# Connector.net
KiCad netlist of a schematic drawn in Altium Designer
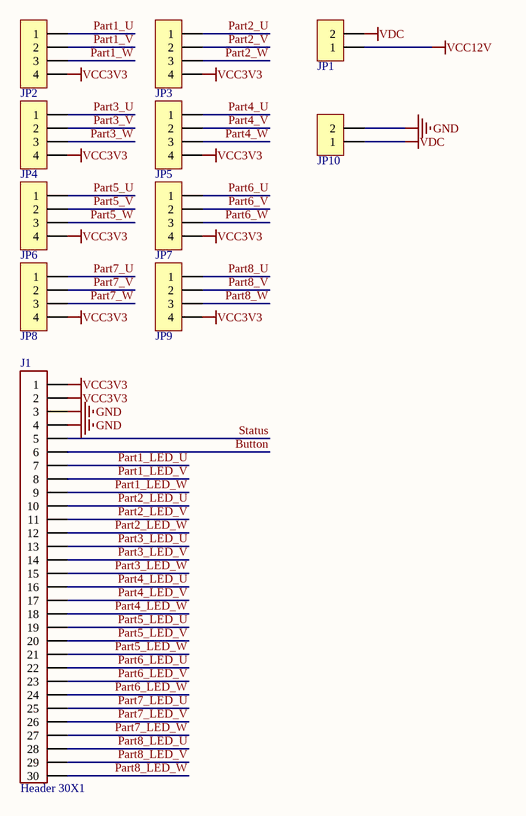
[diagram p0: Connector.SchDoc]

(export (version "E")
  (design (tool "Eeschema 10.0.6"))
  (components
    (comp (ref "J1")
      (value "Header 30X1")
      (footprint "FPC1.0-2H-WS-30P")
      (libsource (lib "Connector-PinHeader") (part "Header 30X1"))
    )
    (comp (ref "JP1")
      (value "HDR-1X2")
      (footprint "XH2.54-LI-2P")
      (description "2P接插件")
      (fields (field (name "版权归属") "源创客"))
      (libsource (lib "Connector-PinHeader") (part "Header 2"))
    )
    (comp (ref "JP2")
      (value "HDR-1X4")
      (footprint "XH2.54-LI-4P")
      (description "4P接插件")
      (fields (field (name "版权归属") "源创客"))
      (libsource (lib "Connector-PinHeader") (part "Header 4"))
    )
    (comp (ref "JP3")
      (value "HDR-1X4")
      (footprint "XH2.54-LI-4P")
      (description "4P接插件")
      (fields (field (name "版权归属") "源创客"))
      (libsource (lib "Connector-PinHeader") (part "Header 4"))
    )
    (comp (ref "JP4")
      (value "HDR-1X4")
      (footprint "XH2.54-LI-4P")
      (description "4P接插件")
      (fields (field (name "版权归属") "源创客"))
      (libsource (lib "Connector-PinHeader") (part "Header 4"))
    )
    (comp (ref "JP5")
      (value "HDR-1X4")
      (footprint "XH2.54-LI-4P")
      (description "4P接插件")
      (fields (field (name "版权归属") "源创客"))
      (libsource (lib "Connector-PinHeader") (part "Header 4"))
    )
    (comp (ref "JP6")
      (value "HDR-1X4")
      (footprint "XH2.54-LI-4P")
      (description "4P接插件")
      (fields (field (name "版权归属") "源创客"))
      (libsource (lib "Connector-PinHeader") (part "Header 4"))
    )
    (comp (ref "JP7")
      (value "HDR-1X4")
      (footprint "XH2.54-LI-4P")
      (description "4P接插件")
      (fields (field (name "版权归属") "源创客"))
      (libsource (lib "Connector-PinHeader") (part "Header 4"))
    )
    (comp (ref "JP8")
      (value "HDR-1X4")
      (footprint "XH2.54-LI-4P")
      (description "4P接插件")
      (fields (field (name "版权归属") "源创客"))
      (libsource (lib "Connector-PinHeader") (part "Header 4"))
    )
    (comp (ref "JP9")
      (value "HDR-1X4")
      (footprint "XH2.54-LI-4P")
      (description "4P接插件")
      (fields (field (name "版权归属") "源创客"))
      (libsource (lib "Connector-PinHeader") (part "Header 4"))
    )
    (comp (ref "JP10")
      (value "HDR-1X2")
      (footprint "XH2.54-LI-2P")
      (description "2P接插件")
      (fields (field (name "版权归属") "源创客"))
      (libsource (lib "Connector-PinHeader") (part "Header 2"))
    )
  )
  (nets
    (net (code "1") (name "/Button") (class "Default")
      (node (ref "J1") (pin "6") (pinfunction "6_6") (pintype "passive"))
    )
    (net (code "2") (name "/Part1_LED_U") (class "Default")
      (node (ref "J1") (pin "7") (pinfunction "7_7") (pintype "passive"))
    )
    (net (code "3") (name "/Part1_LED_V") (class "Default")
      (node (ref "J1") (pin "8") (pinfunction "8_8") (pintype "passive"))
    )
    (net (code "4") (name "/Part1_LED_W") (class "Default")
      (node (ref "J1") (pin "9") (pinfunction "9_9") (pintype "passive"))
    )
    (net (code "5") (name "/Part1_U") (class "Default")
      (node (ref "JP2") (pin "1") (pinfunction "1_1") (pintype "passive"))
    )
    (net (code "6") (name "/Part1_V") (class "Default")
      (node (ref "JP2") (pin "2") (pinfunction "2_2") (pintype "passive"))
    )
    (net (code "7") (name "/Part1_W") (class "Default")
      (node (ref "JP2") (pin "3") (pinfunction "3_3") (pintype "passive"))
    )
    (net (code "8") (name "/Part2_LED_U") (class "Default")
      (node (ref "J1") (pin "10") (pinfunction "10_10") (pintype "passive"))
    )
    (net (code "9") (name "/Part2_LED_V") (class "Default")
      (node (ref "J1") (pin "11") (pinfunction "11_11") (pintype "passive"))
    )
    (net (code "10") (name "/Part2_LED_W") (class "Default")
      (node (ref "J1") (pin "12") (pinfunction "12_12") (pintype "passive"))
    )
    (net (code "11") (name "/Part2_U") (class "Default")
      (node (ref "JP3") (pin "1") (pinfunction "1_1") (pintype "passive"))
    )
    (net (code "12") (name "/Part2_V") (class "Default")
      (node (ref "JP3") (pin "2") (pinfunction "2_2") (pintype "passive"))
    )
    (net (code "13") (name "/Part2_W") (class "Default")
      (node (ref "JP3") (pin "3") (pinfunction "3_3") (pintype "passive"))
    )
    (net (code "14") (name "/Part3_LED_U") (class "Default")
      (node (ref "J1") (pin "13") (pinfunction "13_13") (pintype "passive"))
    )
    (net (code "15") (name "/Part3_LED_V") (class "Default")
      (node (ref "J1") (pin "14") (pinfunction "14_14") (pintype "passive"))
    )
    (net (code "16") (name "/Part3_LED_W") (class "Default")
      (node (ref "J1") (pin "15") (pinfunction "15_15") (pintype "passive"))
    )
    (net (code "17") (name "/Part3_U") (class "Default")
      (node (ref "JP4") (pin "1") (pinfunction "1_1") (pintype "passive"))
    )
    (net (code "18") (name "/Part3_V") (class "Default")
      (node (ref "JP4") (pin "2") (pinfunction "2_2") (pintype "passive"))
    )
    (net (code "19") (name "/Part3_W") (class "Default")
      (node (ref "JP4") (pin "3") (pinfunction "3_3") (pintype "passive"))
    )
    (net (code "20") (name "/Part4_LED_U") (class "Default")
      (node (ref "J1") (pin "16") (pinfunction "16_16") (pintype "passive"))
    )
    (net (code "21") (name "/Part4_LED_V") (class "Default")
      (node (ref "J1") (pin "17") (pinfunction "17_17") (pintype "passive"))
    )
    (net (code "22") (name "/Part4_LED_W") (class "Default")
      (node (ref "J1") (pin "18") (pinfunction "18_18") (pintype "passive"))
    )
    (net (code "23") (name "/Part4_U") (class "Default")
      (node (ref "JP5") (pin "1") (pinfunction "1_1") (pintype "passive"))
    )
    (net (code "24") (name "/Part4_V") (class "Default")
      (node (ref "JP5") (pin "2") (pinfunction "2_2") (pintype "passive"))
    )
    (net (code "25") (name "/Part4_W") (class "Default")
      (node (ref "JP5") (pin "3") (pinfunction "3_3") (pintype "passive"))
    )
    (net (code "26") (name "/Part5_LED_U") (class "Default")
      (node (ref "J1") (pin "19") (pinfunction "19_19") (pintype "passive"))
    )
    (net (code "27") (name "/Part5_LED_V") (class "Default")
      (node (ref "J1") (pin "20") (pinfunction "20_20") (pintype "passive"))
    )
    (net (code "28") (name "/Part5_LED_W") (class "Default")
      (node (ref "J1") (pin "21") (pinfunction "21_21") (pintype "passive"))
    )
    (net (code "29") (name "/Part5_U") (class "Default")
      (node (ref "JP6") (pin "1") (pinfunction "1_1") (pintype "passive"))
    )
    (net (code "30") (name "/Part5_V") (class "Default")
      (node (ref "JP6") (pin "2") (pinfunction "2_2") (pintype "passive"))
    )
    (net (code "31") (name "/Part5_W") (class "Default")
      (node (ref "JP6") (pin "3") (pinfunction "3_3") (pintype "passive"))
    )
    (net (code "32") (name "/Part6_LED_U") (class "Default")
      (node (ref "J1") (pin "22") (pinfunction "22_22") (pintype "passive"))
    )
    (net (code "33") (name "/Part6_LED_V") (class "Default")
      (node (ref "J1") (pin "23") (pinfunction "23_23") (pintype "passive"))
    )
    (net (code "34") (name "/Part6_LED_W") (class "Default")
      (node (ref "J1") (pin "24") (pinfunction "24_24") (pintype "passive"))
    )
    (net (code "35") (name "/Part6_U") (class "Default")
      (node (ref "JP7") (pin "1") (pinfunction "1_1") (pintype "passive"))
    )
    (net (code "36") (name "/Part6_V") (class "Default")
      (node (ref "JP7") (pin "2") (pinfunction "2_2") (pintype "passive"))
    )
    (net (code "37") (name "/Part6_W") (class "Default")
      (node (ref "JP7") (pin "3") (pinfunction "3_3") (pintype "passive"))
    )
    (net (code "38") (name "/Part7_LED_U") (class "Default")
      (node (ref "J1") (pin "25") (pinfunction "25_25") (pintype "passive"))
    )
    (net (code "39") (name "/Part7_LED_V") (class "Default")
      (node (ref "J1") (pin "26") (pinfunction "26_26") (pintype "passive"))
    )
    (net (code "40") (name "/Part7_LED_W") (class "Default")
      (node (ref "J1") (pin "27") (pinfunction "27_27") (pintype "passive"))
    )
    (net (code "41") (name "/Part7_U") (class "Default")
      (node (ref "JP8") (pin "1") (pinfunction "1_1") (pintype "passive"))
    )
    (net (code "42") (name "/Part7_V") (class "Default")
      (node (ref "JP8") (pin "2") (pinfunction "2_2") (pintype "passive"))
    )
    (net (code "43") (name "/Part7_W") (class "Default")
      (node (ref "JP8") (pin "3") (pinfunction "3_3") (pintype "passive"))
    )
    (net (code "44") (name "/Part8_LED_U") (class "Default")
      (node (ref "J1") (pin "28") (pinfunction "28_28") (pintype "passive"))
    )
    (net (code "45") (name "/Part8_LED_V") (class "Default")
      (node (ref "J1") (pin "29") (pinfunction "29_29") (pintype "passive"))
    )
    (net (code "46") (name "/Part8_LED_W") (class "Default")
      (node (ref "J1") (pin "30") (pinfunction "30_30") (pintype "passive"))
    )
    (net (code "47") (name "/Part8_U") (class "Default")
      (node (ref "JP9") (pin "1") (pinfunction "1_1") (pintype "passive"))
    )
    (net (code "48") (name "/Part8_V") (class "Default")
      (node (ref "JP9") (pin "2") (pinfunction "2_2") (pintype "passive"))
    )
    (net (code "49") (name "/Part8_W") (class "Default")
      (node (ref "JP9") (pin "3") (pinfunction "3_3") (pintype "passive"))
    )
    (net (code "50") (name "/Status") (class "Default")
      (node (ref "J1") (pin "5") (pinfunction "5_5") (pintype "passive"))
    )
    (net (code "51") (name "GND") (class "Default")
      (node (ref "J1") (pin "3") (pinfunction "3_3") (pintype "passive"))
      (node (ref "J1") (pin "4") (pinfunction "4_4") (pintype "passive"))
      (node (ref "JP10") (pin "2") (pinfunction "2_2") (pintype "passive"))
    )
    (net (code "52") (name "VCC3V3") (class "Default")
      (node (ref "J1") (pin "1") (pinfunction "1_1") (pintype "passive"))
      (node (ref "J1") (pin "2") (pinfunction "2_2") (pintype "passive"))
      (node (ref "JP2") (pin "4") (pinfunction "4_4") (pintype "passive"))
      (node (ref "JP3") (pin "4") (pinfunction "4_4") (pintype "passive"))
      (node (ref "JP4") (pin "4") (pinfunction "4_4") (pintype "passive"))
      (node (ref "JP5") (pin "4") (pinfunction "4_4") (pintype "passive"))
      (node (ref "JP6") (pin "4") (pinfunction "4_4") (pintype "passive"))
      (node (ref "JP7") (pin "4") (pinfunction "4_4") (pintype "passive"))
      (node (ref "JP8") (pin "4") (pinfunction "4_4") (pintype "passive"))
      (node (ref "JP9") (pin "4") (pinfunction "4_4") (pintype "passive"))
    )
    (net (code "53") (name "VCC12V") (class "Default")
      (node (ref "JP1") (pin "1") (pinfunction "1_1") (pintype "passive"))
    )
    (net (code "54") (name "VDC") (class "Default")
      (node (ref "JP1") (pin "2") (pinfunction "2_2") (pintype "passive"))
      (node (ref "JP10") (pin "1") (pinfunction "1_1") (pintype "passive"))
    )
  )
)
